# M18_36_Potis_V12.net
KiCad netlist of a schematic drawn in EAGLE
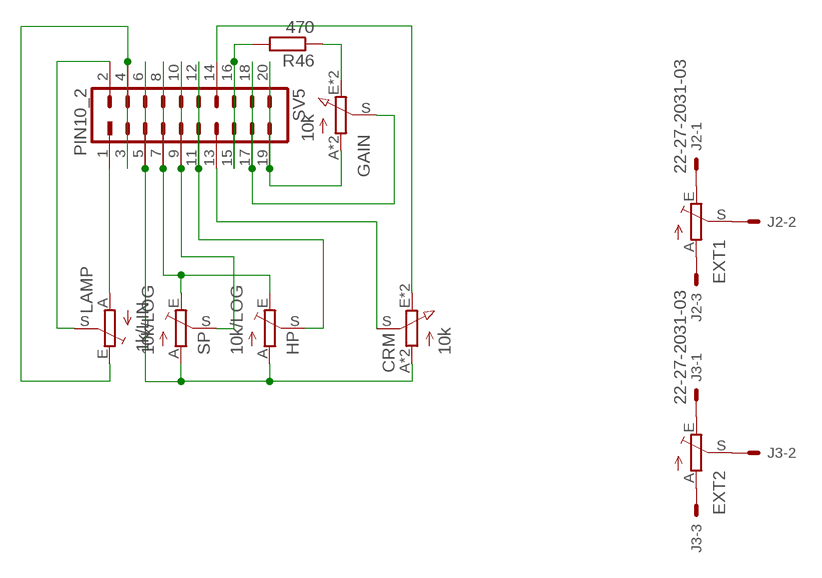
[diagram p0: schematic, sheet 1]

(export (version "E")
  (design (tool "Eeschema 10.0.6"))
  (components
    (comp (ref "CRM")
      (value "10k")
      (footprint "eagle-import:P_PT-10+15_KIEMELT")
      (libsource (lib "eagle-import") (part "P_EUPT10+15_K"))
    )
    (comp (ref "EXT1")
      (value "TRIM_EU-PT10")
      (footprint "eagle-import:PT-10")
      (libsource (lib "eagle-import") (part "TRIM_EU-PT10"))
    )
    (comp (ref "EXT2")
      (value "TRIM_EU-PT10")
      (footprint "eagle-import:PT-10")
      (libsource (lib "eagle-import") (part "TRIM_EU-PT10"))
    )
    (comp (ref "GAIN")
      (value "10k")
      (footprint "eagle-import:P_PT-10+15_KIEMELT")
      (libsource (lib "eagle-import") (part "P_EUPT10+15_K"))
    )
    (comp (ref "HP")
      (value "10k/LOG")
      (footprint "eagle-import:POT_NAR")
      (libsource (lib "eagle-import") (part "TRIM_EU-POT_WHOLE"))
    )
    (comp (ref "J2")
      (value "22-27-2031-03")
      (footprint "eagle-import:6410-03")
      (libsource (lib "eagle-import") (part "22-?-0327-2031"))
    )
    (comp (ref "J3")
      (value "22-27-2031-03")
      (footprint "eagle-import:6410-03")
      (libsource (lib "eagle-import") (part "22-?-0327-2031"))
    )
    (comp (ref "LAMP")
      (value "1k/LIN")
      (footprint "eagle-import:POT_NAR")
      (libsource (lib "eagle-import") (part "TRIM_EU-POT_WHOLE"))
    )
    (comp (ref "R46")
      (value "470")
      (footprint "eagle-import:R0805")
      (libsource (lib "eagle-import") (part "R-EU_R0805"))
    )
    (comp (ref "SP")
      (value "10k/LOG")
      (footprint "eagle-import:POT_NAR")
      (libsource (lib "eagle-import") (part "TRIM_EU-POT_WHOLE"))
    )
    (comp (ref "SV5")
      (value "PIN10_2")
      (footprint "eagle-import:PIN10_2")
      (libsource (lib "eagle-import") (part "PIN10_2"))
    )
  )
  (nets
    (net (code "1") (name "Net-(CRM-A-PadA1)") (class "Default")
      (node (ref "CRM") (pin "A") (pinfunction "A_A") (pintype "passive"))
      (node (ref "CRM") (pin "A1") (pinfunction "A_A1") (pintype "passive"))
      (node (ref "HP") (pin "A") (pinfunction "A_A") (pintype "passive"))
      (node (ref "SP") (pin "A") (pinfunction "A_A") (pintype "passive"))
      (node (ref "SV5") (pin "5") (pinfunction "5_5") (pintype "passive"))
      (node (ref "SV5") (pin "6") (pinfunction "6_6") (pintype "passive"))
    )
    (net (code "2") (name "Net-(CRM-E-PadE1)") (class "Default")
      (node (ref "CRM") (pin "E") (pinfunction "E_E") (pintype "passive"))
      (node (ref "CRM") (pin "E1") (pinfunction "E_E1") (pintype "passive"))
      (node (ref "SV5") (pin "14") (pinfunction "14_14") (pintype "passive"))
    )
    (net (code "3") (name "Net-(CRM-PadS)") (class "Default")
      (node (ref "CRM") (pin "S") (pinfunction "S_S") (pintype "passive"))
      (node (ref "SV5") (pin "13") (pinfunction "13_13") (pintype "passive"))
    )
    (net (code "4") (name "Net-(GAIN-A-PadA1)") (class "Default")
      (node (ref "GAIN") (pin "A") (pinfunction "A_A") (pintype "passive"))
      (node (ref "GAIN") (pin "A1") (pinfunction "A_A1") (pintype "passive"))
      (node (ref "SV5") (pin "19") (pinfunction "19_19") (pintype "passive"))
      (node (ref "SV5") (pin "20") (pinfunction "20_20") (pintype "passive"))
    )
    (net (code "5") (name "Net-(GAIN-E-PadE1)") (class "Default")
      (node (ref "GAIN") (pin "E") (pinfunction "E_E") (pintype "passive"))
      (node (ref "GAIN") (pin "E1") (pinfunction "E_E1") (pintype "passive"))
      (node (ref "R46") (pin "1") (pinfunction "1_1") (pintype "passive"))
    )
    (net (code "6") (name "Net-(GAIN-PadS)") (class "Default")
      (node (ref "GAIN") (pin "S") (pinfunction "S_S") (pintype "passive"))
      (node (ref "SV5") (pin "17") (pinfunction "17_17") (pintype "passive"))
      (node (ref "SV5") (pin "18") (pinfunction "18_18") (pintype "passive"))
    )
    (net (code "7") (name "Net-(HP-PadE)") (class "Default")
      (node (ref "HP") (pin "E") (pinfunction "E_E") (pintype "passive"))
      (node (ref "SP") (pin "E") (pinfunction "E_E") (pintype "passive"))
      (node (ref "SV5") (pin "7") (pinfunction "7_7") (pintype "passive"))
      (node (ref "SV5") (pin "8") (pinfunction "8_8") (pintype "passive"))
    )
    (net (code "8") (name "Net-(HP-PadS)") (class "Default")
      (node (ref "HP") (pin "S") (pinfunction "S_S") (pintype "passive"))
      (node (ref "SV5") (pin "11") (pinfunction "11_11") (pintype "passive"))
      (node (ref "SV5") (pin "12") (pinfunction "12_12") (pintype "passive"))
    )
    (net (code "9") (name "Net-(J2A-S)") (class "Default")
      (node (ref "EXT1") (pin "E") (pinfunction "E_E") (pintype "passive"))
      (node (ref "J2") (pin "1") (pinfunction "S_1") (pintype "passive"))
    )
    (net (code "10") (name "Net-(J2B-S)") (class "Default")
      (node (ref "EXT1") (pin "S") (pinfunction "S_S") (pintype "passive"))
      (node (ref "J2") (pin "2") (pinfunction "S_2") (pintype "passive"))
    )
    (net (code "11") (name "Net-(J2C-S)") (class "Default")
      (node (ref "EXT1") (pin "A") (pinfunction "A_A") (pintype "passive"))
      (node (ref "J2") (pin "3") (pinfunction "S_3") (pintype "passive"))
    )
    (net (code "12") (name "Net-(J3A-S)") (class "Default")
      (node (ref "EXT2") (pin "E") (pinfunction "E_E") (pintype "passive"))
      (node (ref "J3") (pin "1") (pinfunction "S_1") (pintype "passive"))
    )
    (net (code "13") (name "Net-(J3B-S)") (class "Default")
      (node (ref "EXT2") (pin "S") (pinfunction "S_S") (pintype "passive"))
      (node (ref "J3") (pin "2") (pinfunction "S_2") (pintype "passive"))
    )
    (net (code "14") (name "Net-(J3C-S)") (class "Default")
      (node (ref "EXT2") (pin "A") (pinfunction "A_A") (pintype "passive"))
      (node (ref "J3") (pin "3") (pinfunction "S_3") (pintype "passive"))
    )
    (net (code "15") (name "Net-(LAMP-PadA)") (class "Default")
      (node (ref "LAMP") (pin "A") (pinfunction "A_A") (pintype "passive"))
      (node (ref "SV5") (pin "1") (pinfunction "1_1") (pintype "passive"))
    )
    (net (code "16") (name "Net-(LAMP-PadE)") (class "Default")
      (node (ref "LAMP") (pin "E") (pinfunction "E_E") (pintype "passive"))
      (node (ref "SV5") (pin "3") (pinfunction "3_3") (pintype "passive"))
      (node (ref "SV5") (pin "4") (pinfunction "4_4") (pintype "passive"))
    )
    (net (code "17") (name "Net-(LAMP-PadS)") (class "Default")
      (node (ref "LAMP") (pin "S") (pinfunction "S_S") (pintype "passive"))
      (node (ref "SV5") (pin "2") (pinfunction "2_2") (pintype "passive"))
    )
    (net (code "18") (name "Net-(R46-Pad2)") (class "Default")
      (node (ref "R46") (pin "2") (pinfunction "2_2") (pintype "passive"))
      (node (ref "SV5") (pin "15") (pinfunction "15_15") (pintype "passive"))
      (node (ref "SV5") (pin "16") (pinfunction "16_16") (pintype "passive"))
    )
    (net (code "19") (name "Net-(SP-PadS)") (class "Default")
      (node (ref "SP") (pin "S") (pinfunction "S_S") (pintype "passive"))
      (node (ref "SV5") (pin "10") (pinfunction "10_10") (pintype "passive"))
      (node (ref "SV5") (pin "9") (pinfunction "9_9") (pintype "passive"))
    )
  )
)
